# Hall_module.net
KiCad netlist of a schematic drawn in Altium Designer
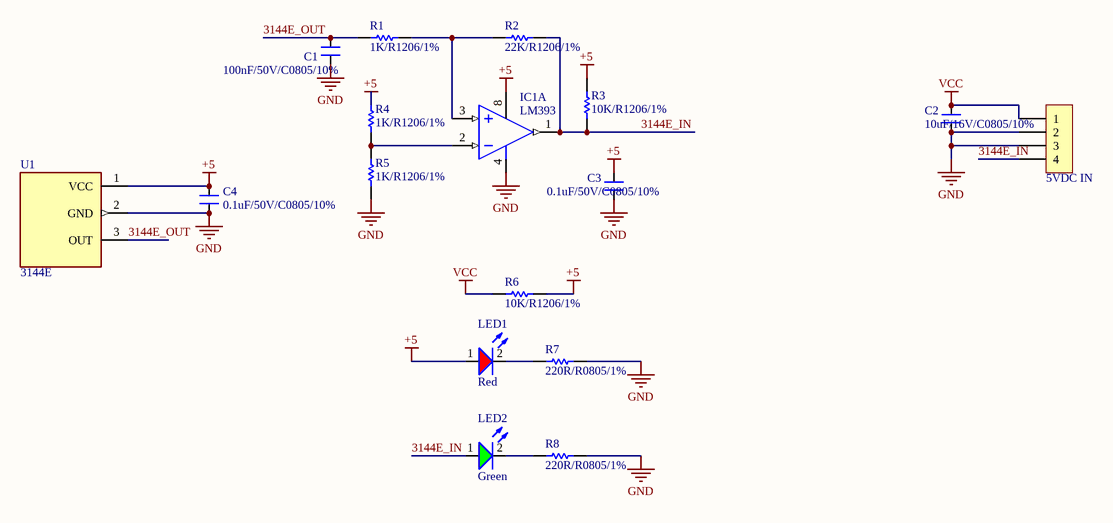
[diagram p0: Hall_module.SchDoc]

(export (version "E")
  (design (tool "Eeschema 10.0.6"))
  (components
    (comp (ref "C1")
      (value "100nF/50V/C0805/10%")
      (footprint "CAP_CERA_C2012(CC0805INCH)")
      (description "CERAMIC CAP 0805")
      (libsource (lib "LPSON") (part "CAP CERA 0805"))
    )
    (comp (ref "C2")
      (value "10uF/16V/C0805/10%")
      (footprint "CAP_CERA_C2012(CC0805INCH)")
      (description "CERAMIC CAP 0805")
      (libsource (lib "LPSON") (part "CAP CERA 0805"))
    )
    (comp (ref "C3")
      (value "0.1uF/50V/C0805/10%")
      (footprint "CAP_CERA_C2012(CC0805INCH)")
      (description "CERAMIC CAP 0805")
      (libsource (lib "LPSON") (part "CAP CERA 0805"))
    )
    (comp (ref "C4")
      (value "0.1uF/50V/C0805/10%")
      (footprint "CAP_CERA_C2012(CC0805INCH)")
      (description "CERAMIC CAP 0805")
      (libsource (lib "LPSON") (part "CAP CERA 0805"))
    )
    (comp (ref "H1")
      (value "5VDC IN")
      (footprint "XH2.54M-4")
      (description "Cắm")
      (libsource (lib "Altium_Lib_by_KhueNguyenCreator") (part "Header 4P 2.54 Duc Thang"))
    )
    (comp (ref "IC1")
      (value "LM393")
      (footprint "U_LM393_DIP8_THT")
      (description "Low-Power Dual Operational Amplifier")
      (libsource (lib "LPSON") (part "LM358"))
    )
    (comp (ref "LED1")
      (value "Red")
      (footprint "Led 0805R")
      (description "LED Red 2mA 1.8V 0805")
      (fields (field (name "Comment") "LED-0805RVC"))
      (libsource (lib "LPSON") (part "LED-0805RVC"))
    )
    (comp (ref "LED2")
      (value "Green")
      (footprint "Led 0805G")
      (description "LED Green 2mA 3V 0805")
      (fields (field (name "Comment") "LED-0805GVC"))
      (libsource (lib "LPSON") (part "LED-0805GVC"))
    )
    (comp (ref "R1")
      (value "1K/R1206/1%")
      (footprint "Res 1206 SMD")
      (description "RES SMD 10K OHM 1% 1206")
      (fields
        (field (name "MANUFACTURER") "Yageo")
        (field (name "MANUFACTURER PART NUMBER") "RC1206FR-075R1L")
      )
      (libsource (lib "LPSON") (part "RES-1206"))
    )
    (comp (ref "R2")
      (value "22K/R1206/1%")
      (footprint "Res 1206 SMD")
      (description "RES SMD 10K OHM 1% 1206")
      (fields
        (field (name "MANUFACTURER") "Yageo")
        (field (name "MANUFACTURER PART NUMBER") "RC1206FR-075R1L")
      )
      (libsource (lib "LPSON") (part "RES-1206"))
    )
    (comp (ref "R3")
      (value "10K/R1206/1%")
      (footprint "Res 1206 SMD")
      (description "RES SMD 10K OHM 1% 1206")
      (fields
        (field (name "MANUFACTURER") "Yageo")
        (field (name "MANUFACTURER PART NUMBER") "RC1206FR-075R1L")
      )
      (libsource (lib "LPSON") (part "RES-1206"))
    )
    (comp (ref "R4")
      (value "1K/R1206/1%")
      (footprint "Res 1206 SMD")
      (description "RES SMD 10K OHM 1% 1206")
      (fields
        (field (name "MANUFACTURER") "Yageo")
        (field (name "MANUFACTURER PART NUMBER") "RC1206FR-075R1L")
      )
      (libsource (lib "LPSON") (part "RES-1206"))
    )
    (comp (ref "R5")
      (value "1K/R1206/1%")
      (footprint "Res 1206 SMD")
      (description "RES SMD 10K OHM 1% 1206")
      (fields
        (field (name "MANUFACTURER") "Yageo")
        (field (name "MANUFACTURER PART NUMBER") "RC1206FR-075R1L")
      )
      (libsource (lib "LPSON") (part "RES-1206"))
    )
    (comp (ref "R6")
      (value "10K/R1206/1%")
      (footprint "Res 1206 SMD")
      (description "RES SMD 10K OHM 1% 1206")
      (fields
        (field (name "MANUFACTURER") "Yageo")
        (field (name "MANUFACTURER PART NUMBER") "RC1206FR-075R1L")
      )
      (libsource (lib "LPSON") (part "RES-1206"))
    )
    (comp (ref "R7")
      (value "220R/R0805/1%")
      (footprint "Res 0805 SMD")
      (description "Thick Film Resistors - SMD 34.8K OHM 1% 0805")
      (fields
        (field (name "MANUFACTURER") "Yageo")
        (field (name "MANUFACTURER PART NUMBER") "RC0603FR-0734K8L")
      )
      (libsource (lib "LPSON") (part "34.8K/R0805/1%"))
    )
    (comp (ref "R8")
      (value "220R/R0805/1%")
      (footprint "Res 0805 SMD")
      (description "Thick Film Resistors - SMD 34.8K OHM 1% 0805")
      (fields
        (field (name "MANUFACTURER") "Yageo")
        (field (name "MANUFACTURER PART NUMBER") "RC0603FR-0734K8L")
      )
      (libsource (lib "LPSON") (part "34.8K/R0805/1%"))
    )
    (comp (ref "U1")
      (value "3144E")
      (footprint "U_3144E")
      (description "Digital hall sensor switch Open Collector Hall Effect")
      (fields (field (name "MF") "Honeywell Sensing") (field (name "MP") "SS541AT"))
      (libsource (lib "SS541AT") (part "SS541AT"))
    )
  )
  (nets
    (net (code "1") (name "+5") (class "Default")
      (node (ref "C3") (pin "1") (pinfunction "1_1") (pintype "passive"))
      (node (ref "C4") (pin "1") (pinfunction "1_1") (pintype "passive"))
      (node (ref "IC1") (pin "8") (pinfunction "+V_8") (pintype "passive"))
      (node (ref "LED1") (pin "1") (pinfunction "A_1") (pintype "passive"))
      (node (ref "R3") (pin "1") (pinfunction "1_1") (pintype "passive"))
      (node (ref "R4") (pin "1") (pinfunction "1_1") (pintype "passive"))
      (node (ref "R6") (pin "2") (pinfunction "2_2") (pintype "passive"))
      (node (ref "U1") (pin "1") (pinfunction "VCC_1") (pintype "power_in"))
    )
    (net (code "2") (name "/3144E_IN") (class "Default")
      (node (ref "H1") (pin "4") (pinfunction "4_4") (pintype "passive"))
      (node (ref "IC1") (pin "1") (pinfunction "OUT_1") (pintype "output"))
      (node (ref "LED2") (pin "1") (pinfunction "A_1") (pintype "passive"))
      (node (ref "R2") (pin "2") (pinfunction "2_2") (pintype "passive"))
      (node (ref "R3") (pin "2") (pinfunction "2_2") (pintype "passive"))
    )
    (net (code "3") (name "/3144E_OUT") (class "Default")
      (node (ref "C1") (pin "2") (pinfunction "2_2") (pintype "passive"))
      (node (ref "R1") (pin "2") (pinfunction "2_2") (pintype "passive"))
      (node (ref "U1") (pin "3") (pinfunction "OUT_3") (pintype "power_in"))
    )
    (net (code "4") (name "GND") (class "Default")
      (node (ref "C1") (pin "1") (pinfunction "1_1") (pintype "passive"))
      (node (ref "C2") (pin "1") (pinfunction "1_1") (pintype "passive"))
      (node (ref "C3") (pin "2") (pinfunction "2_2") (pintype "passive"))
      (node (ref "C4") (pin "2") (pinfunction "2_2") (pintype "passive"))
      (node (ref "H1") (pin "2") (pinfunction "2_2") (pintype "passive"))
      (node (ref "H1") (pin "3") (pinfunction "3_3") (pintype "passive"))
      (node (ref "IC1") (pin "4") (pinfunction "-V_4") (pintype "passive"))
      (node (ref "R5") (pin "2") (pinfunction "2_2") (pintype "passive"))
      (node (ref "R7") (pin "2") (pinfunction "2_2") (pintype "passive"))
      (node (ref "R8") (pin "2") (pinfunction "2_2") (pintype "passive"))
      (node (ref "U1") (pin "2") (pinfunction "GND_2") (pintype "output"))
    )
    (net (code "5") (name "Net-(IC1A-IN+)") (class "Default")
      (node (ref "IC1") (pin "3") (pinfunction "IN+_3") (pintype "input"))
      (node (ref "R1") (pin "1") (pinfunction "1_1") (pintype "passive"))
      (node (ref "R2") (pin "1") (pinfunction "1_1") (pintype "passive"))
    )
    (net (code "6") (name "Net-(IC1A-IN-)") (class "Default")
      (node (ref "IC1") (pin "2") (pinfunction "IN-_2") (pintype "input"))
      (node (ref "R4") (pin "2") (pinfunction "2_2") (pintype "passive"))
      (node (ref "R5") (pin "1") (pinfunction "1_1") (pintype "passive"))
    )
    (net (code "7") (name "Net-(LED1-K)") (class "Default")
      (node (ref "LED1") (pin "2") (pinfunction "K_2") (pintype "passive"))
      (node (ref "R7") (pin "1") (pinfunction "1_1") (pintype "passive"))
    )
    (net (code "8") (name "Net-(LED2-K)") (class "Default")
      (node (ref "LED2") (pin "2") (pinfunction "K_2") (pintype "passive"))
      (node (ref "R8") (pin "1") (pinfunction "1_1") (pintype "passive"))
    )
    (net (code "9") (name "VCC") (class "Default")
      (node (ref "C2") (pin "2") (pinfunction "2_2") (pintype "passive"))
      (node (ref "H1") (pin "1") (pinfunction "1_1") (pintype "passive"))
      (node (ref "R6") (pin "1") (pinfunction "1_1") (pintype "passive"))
    )
  )
)
